# STorM32_NT_mpu_module_v007-mpu6000.net
KiCad netlist of a schematic drawn in EAGLE
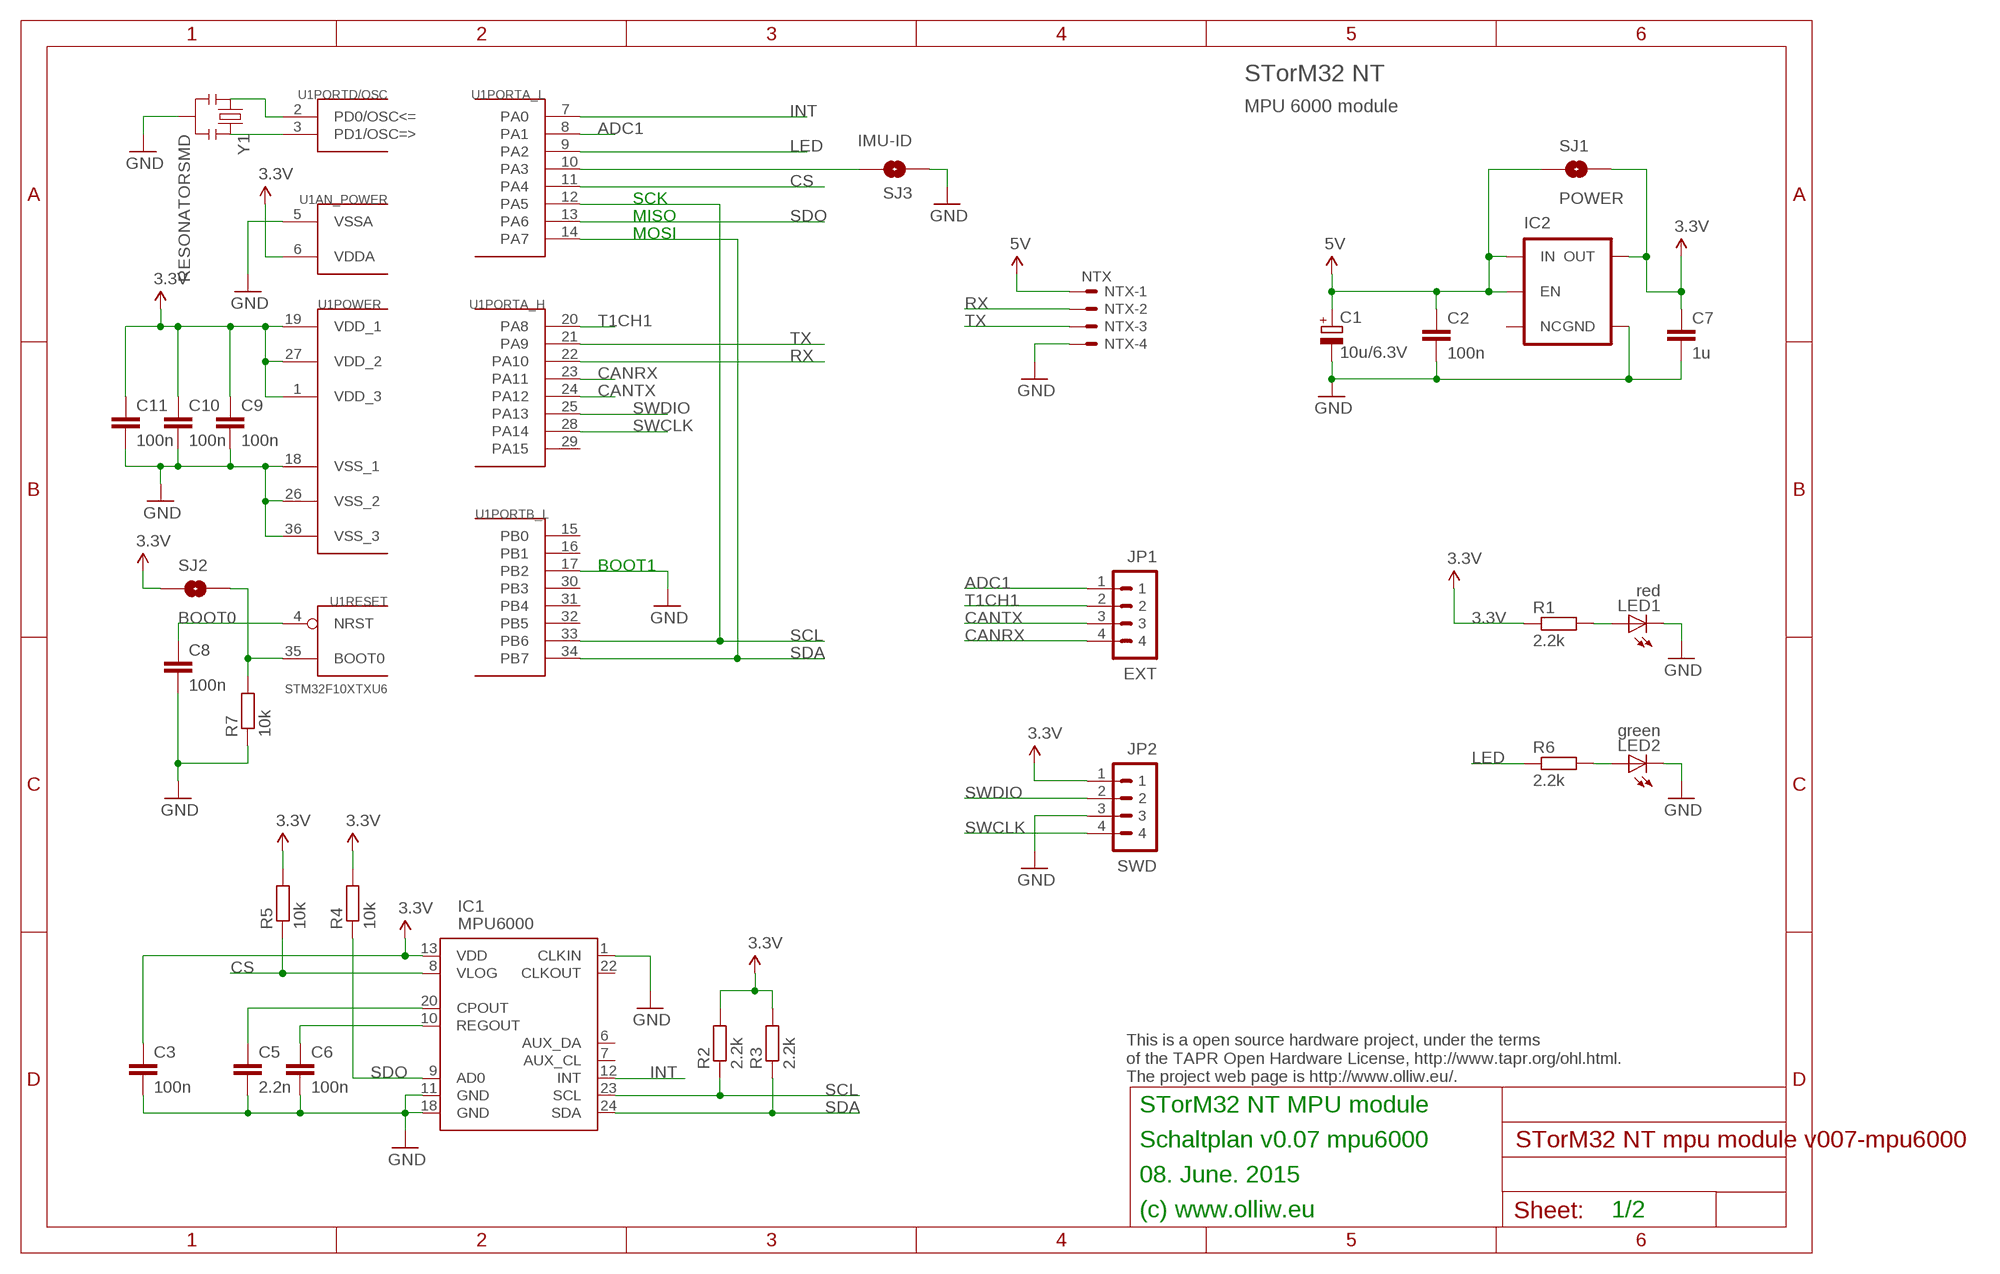
[diagram p0: schematic, sheet 1]

(export (version "E")
  (design (tool "Eeschema 10.0.6"))
  (components
    (comp (ref "C1")
      (value "10u/6.3V")
      (footprint "eagle-import:SMC_B")
      (libsource (lib "eagle-import") (part "CPOL-EUSMCB"))
    )
    (comp (ref "C2")
      (value "100n")
      (footprint "eagle-import:C0603")
      (libsource (lib "eagle-import") (part "C-EUC0603"))
    )
    (comp (ref "C3")
      (value "100n")
      (footprint "eagle-import:C0603")
      (libsource (lib "eagle-import") (part "C-EUC0603"))
    )
    (comp (ref "C5")
      (value "2.2n")
      (footprint "eagle-import:C0603")
      (libsource (lib "eagle-import") (part "C-EUC0603"))
    )
    (comp (ref "C6")
      (value "100n")
      (footprint "eagle-import:C0603")
      (libsource (lib "eagle-import") (part "C-EUC0603"))
    )
    (comp (ref "C7")
      (value "1u")
      (footprint "eagle-import:C0603")
      (libsource (lib "eagle-import") (part "C-EUC0603"))
    )
    (comp (ref "C8")
      (value "100n")
      (footprint "eagle-import:C0402")
      (libsource (lib "eagle-import") (part "C-EUC0402"))
    )
    (comp (ref "C9")
      (value "100n")
      (footprint "eagle-import:C0603")
      (libsource (lib "eagle-import") (part "C-EUC0603"))
    )
    (comp (ref "C10")
      (value "100n")
      (footprint "eagle-import:C0402")
      (libsource (lib "eagle-import") (part "C-EUC0402"))
    )
    (comp (ref "C11")
      (value "100n")
      (footprint "eagle-import:C0603")
      (libsource (lib "eagle-import") (part "C-EUC0603"))
    )
    (comp (ref "IC1")
      (value "MPU6000")
      (footprint "eagle-import:QFN-24")
      (libsource (lib "eagle-import") (part "IMU3000"))
    )
    (comp (ref "IC2")
      (value "V_REG_TPS76433SOT23-5")
      (footprint "eagle-import:SOT23-5")
      (libsource (lib "eagle-import") (part "V_REG_TPS76433SOT23-5"))
    )
    (comp (ref "JP1")
      (value "EXT")
      (footprint "eagle-import:4X1_1P27_OCT_BILEX")
      (libsource (lib "eagle-import") (part "P4X1_1P27-OCT_BILEX"))
    )
    (comp (ref "JP2")
      (value "SWD")
      (footprint "eagle-import:4X1_1P27_OCT_BILEX")
      (libsource (lib "eagle-import") (part "P4X1_1P27-OCT_BILEX"))
    )
    (comp (ref "LED1")
      (value "red")
      (footprint "eagle-import:CHIPLED_0603")
      (libsource (lib "eagle-import") (part "LEDCHIPLED_0603"))
    )
    (comp (ref "LED2")
      (value "green")
      (footprint "eagle-import:CHIPLED_0603")
      (libsource (lib "eagle-import") (part "LEDCHIPLED_0603"))
    )
    (comp (ref "NTX")
      (value "NTX")
      (footprint "eagle-import:SM04B-SRSS-TB")
      (libsource (lib "eagle-import") (part "?M04B-SRSS-TBS"))
    )
    (comp (ref "R1")
      (value "2.2k")
      (footprint "eagle-import:R0603")
      (libsource (lib "eagle-import") (part "R-EU_R0603"))
    )
    (comp (ref "R2")
      (value "2.2k")
      (footprint "eagle-import:R0603")
      (libsource (lib "eagle-import") (part "R-EU_R0603"))
    )
    (comp (ref "R3")
      (value "2.2k")
      (footprint "eagle-import:R0603")
      (libsource (lib "eagle-import") (part "R-EU_R0603"))
    )
    (comp (ref "R4")
      (value "10k")
      (footprint "eagle-import:R0603")
      (libsource (lib "eagle-import") (part "R-EU_R0603"))
    )
    (comp (ref "R5")
      (value "10k")
      (footprint "eagle-import:R0603")
      (libsource (lib "eagle-import") (part "R-EU_R0603"))
    )
    (comp (ref "R6")
      (value "2.2k")
      (footprint "eagle-import:R0603")
      (libsource (lib "eagle-import") (part "R-EU_R0603"))
    )
    (comp (ref "R7")
      (value "10k")
      (footprint "eagle-import:R0603")
      (libsource (lib "eagle-import") (part "R-EU_R0603"))
    )
    (comp (ref "SJ1")
      (value "POWER")
      (footprint "eagle-import:SJ_2S-NO")
      (libsource (lib "eagle-import") (part "SOLDERJUMPERNO"))
    )
    (comp (ref "SJ2")
      (value "BOOT0")
      (footprint "eagle-import:SJ_2S-NO")
      (libsource (lib "eagle-import") (part "SOLDERJUMPERNO"))
    )
    (comp (ref "SJ3")
      (value "IMU-ID")
      (footprint "eagle-import:SJ_2S-NO")
      (libsource (lib "eagle-import") (part "SOLDERJUMPERNO"))
    )
    (comp (ref "U1")
      (value "STM32F10XTXU6")
      (footprint "eagle-import:VFQFPN36")
      (libsource (lib "eagle-import") (part "STM32F10XTXU6"))
    )
    (comp (ref "Y1")
      (value "RESONATORSMD")
      (footprint "eagle-import:RESONATOR-SMD")
      (libsource (lib "eagle-import") (part "RESONATORSMD"))
    )
  )
  (nets
    (net (code "1") (name "/ADC1") (class "Default")
      (node (ref "JP1") (pin "1") (pinfunction "1_1") (pintype "passive"))
      (node (ref "U1") (pin "8") (pinfunction "PA1_8") (pintype "bidirectional"))
    )
    (net (code "2") (name "/CANRX") (class "Default")
      (node (ref "JP1") (pin "4") (pinfunction "4_4") (pintype "passive"))
      (node (ref "U1") (pin "23") (pinfunction "PA11_23") (pintype "bidirectional"))
    )
    (net (code "3") (name "/CANTX") (class "Default")
      (node (ref "JP1") (pin "3") (pinfunction "3_3") (pintype "passive"))
      (node (ref "U1") (pin "24") (pinfunction "PA12_24") (pintype "bidirectional"))
    )
    (net (code "4") (name "/CS") (class "Default")
      (node (ref "IC1") (pin "8") (pinfunction "VLOG_8") (pintype "bidirectional"))
      (node (ref "R5") (pin "1") (pinfunction "1_1") (pintype "passive"))
      (node (ref "U1") (pin "11") (pinfunction "PA4_11") (pintype "bidirectional"))
    )
    (net (code "5") (name "/INT") (class "Default")
      (node (ref "IC1") (pin "12") (pinfunction "INT_12") (pintype "bidirectional"))
      (node (ref "U1") (pin "7") (pinfunction "PA0_7") (pintype "bidirectional"))
    )
    (net (code "6") (name "/LED") (class "Default")
      (node (ref "R6") (pin "1") (pinfunction "1_1") (pintype "passive"))
      (node (ref "U1") (pin "9") (pinfunction "PA2_9") (pintype "bidirectional"))
    )
    (net (code "7") (name "/RX") (class "Default")
      (node (ref "NTX") (pin "2") (pinfunction "S_2") (pintype "passive"))
      (node (ref "U1") (pin "22") (pinfunction "PA10_22") (pintype "bidirectional"))
    )
    (net (code "8") (name "/SCL") (class "Default")
      (node (ref "IC1") (pin "23") (pinfunction "SCL_23") (pintype "bidirectional"))
      (node (ref "R2") (pin "1") (pinfunction "1_1") (pintype "passive"))
      (node (ref "U1") (pin "12") (pinfunction "PA5_12") (pintype "bidirectional"))
      (node (ref "U1") (pin "33") (pinfunction "PB6_33") (pintype "bidirectional"))
    )
    (net (code "9") (name "/SDA") (class "Default")
      (node (ref "IC1") (pin "24") (pinfunction "SDA_24") (pintype "bidirectional"))
      (node (ref "R3") (pin "1") (pinfunction "1_1") (pintype "passive"))
      (node (ref "U1") (pin "14") (pinfunction "PA7_14") (pintype "bidirectional"))
      (node (ref "U1") (pin "34") (pinfunction "PB7_34") (pintype "bidirectional"))
    )
    (net (code "10") (name "/SDO") (class "Default")
      (node (ref "IC1") (pin "9") (pinfunction "AD0_9") (pintype "bidirectional"))
      (node (ref "R4") (pin "1") (pinfunction "1_1") (pintype "passive"))
      (node (ref "U1") (pin "13") (pinfunction "PA6_13") (pintype "bidirectional"))
    )
    (net (code "11") (name "/SWCLK") (class "Default")
      (node (ref "JP2") (pin "4") (pinfunction "4_4") (pintype "passive"))
      (node (ref "U1") (pin "28") (pinfunction "PA14_28") (pintype "bidirectional"))
    )
    (net (code "12") (name "/SWDIO") (class "Default")
      (node (ref "JP2") (pin "2") (pinfunction "2_2") (pintype "passive"))
      (node (ref "U1") (pin "25") (pinfunction "PA13_25") (pintype "bidirectional"))
    )
    (net (code "13") (name "/T1CH1") (class "Default")
      (node (ref "JP1") (pin "2") (pinfunction "2_2") (pintype "passive"))
      (node (ref "U1") (pin "20") (pinfunction "PA8_20") (pintype "bidirectional"))
    )
    (net (code "14") (name "/TX") (class "Default")
      (node (ref "NTX") (pin "3") (pinfunction "S_3") (pintype "passive"))
      (node (ref "U1") (pin "21") (pinfunction "PA9_21") (pintype "bidirectional"))
    )
    (net (code "15") (name "3.3V") (class "Default")
      (node (ref "C10") (pin "1") (pinfunction "1_1") (pintype "passive"))
      (node (ref "C11") (pin "1") (pinfunction "1_1") (pintype "passive"))
      (node (ref "C3") (pin "1") (pinfunction "1_1") (pintype "passive"))
      (node (ref "C7") (pin "1") (pinfunction "1_1") (pintype "passive"))
      (node (ref "C9") (pin "1") (pinfunction "1_1") (pintype "passive"))
      (node (ref "IC1") (pin "13") (pinfunction "VDD_13") (pintype "bidirectional"))
      (node (ref "IC2") (pin "5") (pinfunction "OUT_5") (pintype "passive"))
      (node (ref "JP2") (pin "1") (pinfunction "1_1") (pintype "passive"))
      (node (ref "R1") (pin "1") (pinfunction "1_1") (pintype "passive"))
      (node (ref "R2") (pin "2") (pinfunction "2_2") (pintype "passive"))
      (node (ref "R3") (pin "2") (pinfunction "2_2") (pintype "passive"))
      (node (ref "R4") (pin "2") (pinfunction "2_2") (pintype "passive"))
      (node (ref "R5") (pin "2") (pinfunction "2_2") (pintype "passive"))
      (node (ref "SJ1") (pin "2") (pinfunction "2_2") (pintype "passive"))
      (node (ref "SJ2") (pin "1") (pinfunction "1_1") (pintype "passive"))
      (node (ref "U1") (pin "1") (pinfunction "VDD_3_1") (pintype "power_in"))
      (node (ref "U1") (pin "19") (pinfunction "VDD_1_19") (pintype "power_in"))
      (node (ref "U1") (pin "27") (pinfunction "VDD_2_27") (pintype "power_in"))
      (node (ref "U1") (pin "6") (pinfunction "VDDA_6") (pintype "power_in"))
    )
    (net (code "16") (name "5V") (class "Default")
      (node (ref "C1") (pin "+") (pinfunction "+_+") (pintype "passive"))
      (node (ref "C2") (pin "1") (pinfunction "1_1") (pintype "passive"))
      (node (ref "IC2") (pin "1") (pinfunction "IN_1") (pintype "input"))
      (node (ref "IC2") (pin "3") (pinfunction "EN_3") (pintype "input"))
      (node (ref "NTX") (pin "1") (pinfunction "S_1") (pintype "passive"))
      (node (ref "SJ1") (pin "1") (pinfunction "1_1") (pintype "passive"))
    )
    (net (code "17") (name "GND") (class "Default")
      (node (ref "C1") (pin "-") (pinfunction "-_-") (pintype "passive"))
      (node (ref "C10") (pin "2") (pinfunction "2_2") (pintype "passive"))
      (node (ref "C11") (pin "2") (pinfunction "2_2") (pintype "passive"))
      (node (ref "C2") (pin "2") (pinfunction "2_2") (pintype "passive"))
      (node (ref "C3") (pin "2") (pinfunction "2_2") (pintype "passive"))
      (node (ref "C5") (pin "2") (pinfunction "2_2") (pintype "passive"))
      (node (ref "C6") (pin "2") (pinfunction "2_2") (pintype "passive"))
      (node (ref "C7") (pin "2") (pinfunction "2_2") (pintype "passive"))
      (node (ref "C8") (pin "2") (pinfunction "2_2") (pintype "passive"))
      (node (ref "C9") (pin "2") (pinfunction "2_2") (pintype "passive"))
      (node (ref "IC1") (pin "1") (pinfunction "CLKIN_1") (pintype "bidirectional"))
      (node (ref "IC1") (pin "11") (pinfunction "GND_11") (pintype "bidirectional"))
      (node (ref "IC1") (pin "18") (pinfunction "GND_18") (pintype "bidirectional"))
      (node (ref "IC2") (pin "2") (pinfunction "GND_2") (pintype "input"))
      (node (ref "JP2") (pin "3") (pinfunction "3_3") (pintype "passive"))
      (node (ref "LED1") (pin "C") (pinfunction "C_C") (pintype "passive"))
      (node (ref "LED2") (pin "C") (pinfunction "C_C") (pintype "passive"))
      (node (ref "NTX") (pin "4") (pinfunction "S_4") (pintype "passive"))
      (node (ref "R7") (pin "1") (pinfunction "1_1") (pintype "passive"))
      (node (ref "SJ3") (pin "1") (pinfunction "1_1") (pintype "passive"))
      (node (ref "U1") (pin "17") (pinfunction "PB2_17") (pintype "bidirectional"))
      (node (ref "U1") (pin "18") (pinfunction "VSS_1_18") (pintype "power_in"))
      (node (ref "U1") (pin "26") (pinfunction "VSS_2_26") (pintype "power_in"))
      (node (ref "U1") (pin "36") (pinfunction "VSS_3_36") (pintype "power_in"))
      (node (ref "U1") (pin "5") (pinfunction "VSSA_5") (pintype "power_in"))
      (node (ref "Y1") (pin "2") (pinfunction "2_2") (pintype "passive"))
    )
    (net (code "18") (name "Net-(IC1-CPOUT)") (class "Default")
      (node (ref "C5") (pin "1") (pinfunction "1_1") (pintype "passive"))
      (node (ref "IC1") (pin "20") (pinfunction "CPOUT_20") (pintype "bidirectional"))
    )
    (net (code "19") (name "Net-(IC1-REGOUT)") (class "Default")
      (node (ref "C6") (pin "1") (pinfunction "1_1") (pintype "passive"))
      (node (ref "IC1") (pin "10") (pinfunction "REGOUT_10") (pintype "bidirectional"))
    )
    (net (code "20") (name "Net-(LED1-PadA)") (class "Default")
      (node (ref "LED1") (pin "A") (pinfunction "A_A") (pintype "passive"))
      (node (ref "R1") (pin "2") (pinfunction "2_2") (pintype "passive"))
    )
    (net (code "21") (name "Net-(LED2-PadA)") (class "Default")
      (node (ref "LED2") (pin "A") (pinfunction "A_A") (pintype "passive"))
      (node (ref "R6") (pin "2") (pinfunction "2_2") (pintype "passive"))
    )
    (net (code "22") (name "Net-(U1C-PA3)") (class "Default")
      (node (ref "SJ3") (pin "2") (pinfunction "2_2") (pintype "passive"))
      (node (ref "U1") (pin "10") (pinfunction "PA3_10") (pintype "bidirectional"))
    )
    (net (code "23") (name "Net-(U1E-PD0{slash}OSC<=)") (class "Default")
      (node (ref "U1") (pin "2") (pinfunction "PD0/OSC<=_2") (pintype "bidirectional"))
      (node (ref "Y1") (pin "1") (pinfunction "1_1") (pintype "passive"))
    )
    (net (code "24") (name "Net-(U1E-PD1{slash}OSC=>)") (class "Default")
      (node (ref "U1") (pin "3") (pinfunction "PD1/OSC=>_3") (pintype "bidirectional"))
      (node (ref "Y1") (pin "3") (pinfunction "3_3") (pintype "passive"))
    )
    (net (code "25") (name "Net-(U1G-BOOT0)") (class "Default")
      (node (ref "R7") (pin "2") (pinfunction "2_2") (pintype "passive"))
      (node (ref "SJ2") (pin "2") (pinfunction "2_2") (pintype "passive"))
      (node (ref "U1") (pin "35") (pinfunction "BOOT0_35") (pintype "input"))
    )
    (net (code "26") (name "Net-(U1G-NRST)") (class "Default")
      (node (ref "C8") (pin "1") (pinfunction "1_1") (pintype "passive"))
      (node (ref "U1") (pin "4") (pinfunction "NRST_4") (pintype "input"))
    )
    (net (code "27") (name "unconnected-(IC1-AUX_CL-Pad7)") (class "Default")
      (node (ref "IC1") (pin "7") (pinfunction "AUX_CL_7") (pintype "bidirectional"))
    )
    (net (code "28") (name "unconnected-(IC1-AUX_DA-Pad6)") (class "Default")
      (node (ref "IC1") (pin "6") (pinfunction "AUX_DA_6") (pintype "bidirectional"))
    )
    (net (code "29") (name "unconnected-(IC1-CLKOUT-Pad22)") (class "Default")
      (node (ref "IC1") (pin "22") (pinfunction "CLKOUT_22") (pintype "bidirectional"))
    )
    (net (code "30") (name "unconnected-(IC2-NC-Pad4)") (class "Default")
      (node (ref "IC2") (pin "4") (pinfunction "NC_4") (pintype "input"))
    )
    (net (code "31") (name "unconnected-(U1B-PA15-Pad29)") (class "Default")
      (node (ref "U1") (pin "29") (pinfunction "PA15_29") (pintype "bidirectional"))
    )
    (net (code "32") (name "unconnected-(U1D-PB0-Pad15)") (class "Default")
      (node (ref "U1") (pin "15") (pinfunction "PB0_15") (pintype "bidirectional"))
    )
    (net (code "33") (name "unconnected-(U1D-PB1-Pad16)") (class "Default")
      (node (ref "U1") (pin "16") (pinfunction "PB1_16") (pintype "bidirectional"))
    )
    (net (code "34") (name "unconnected-(U1D-PB3-Pad30)") (class "Default")
      (node (ref "U1") (pin "30") (pinfunction "PB3_30") (pintype "bidirectional"))
    )
    (net (code "35") (name "unconnected-(U1D-PB4-Pad31)") (class "Default")
      (node (ref "U1") (pin "31") (pinfunction "PB4_31") (pintype "bidirectional"))
    )
    (net (code "36") (name "unconnected-(U1D-PB5-Pad32)") (class "Default")
      (node (ref "U1") (pin "32") (pinfunction "PB5_32") (pintype "bidirectional"))
    )
  )
)
